# Own_18650_Board_v1_1_Final_AR.net
KiCad netlist of a schematic drawn in EAGLE
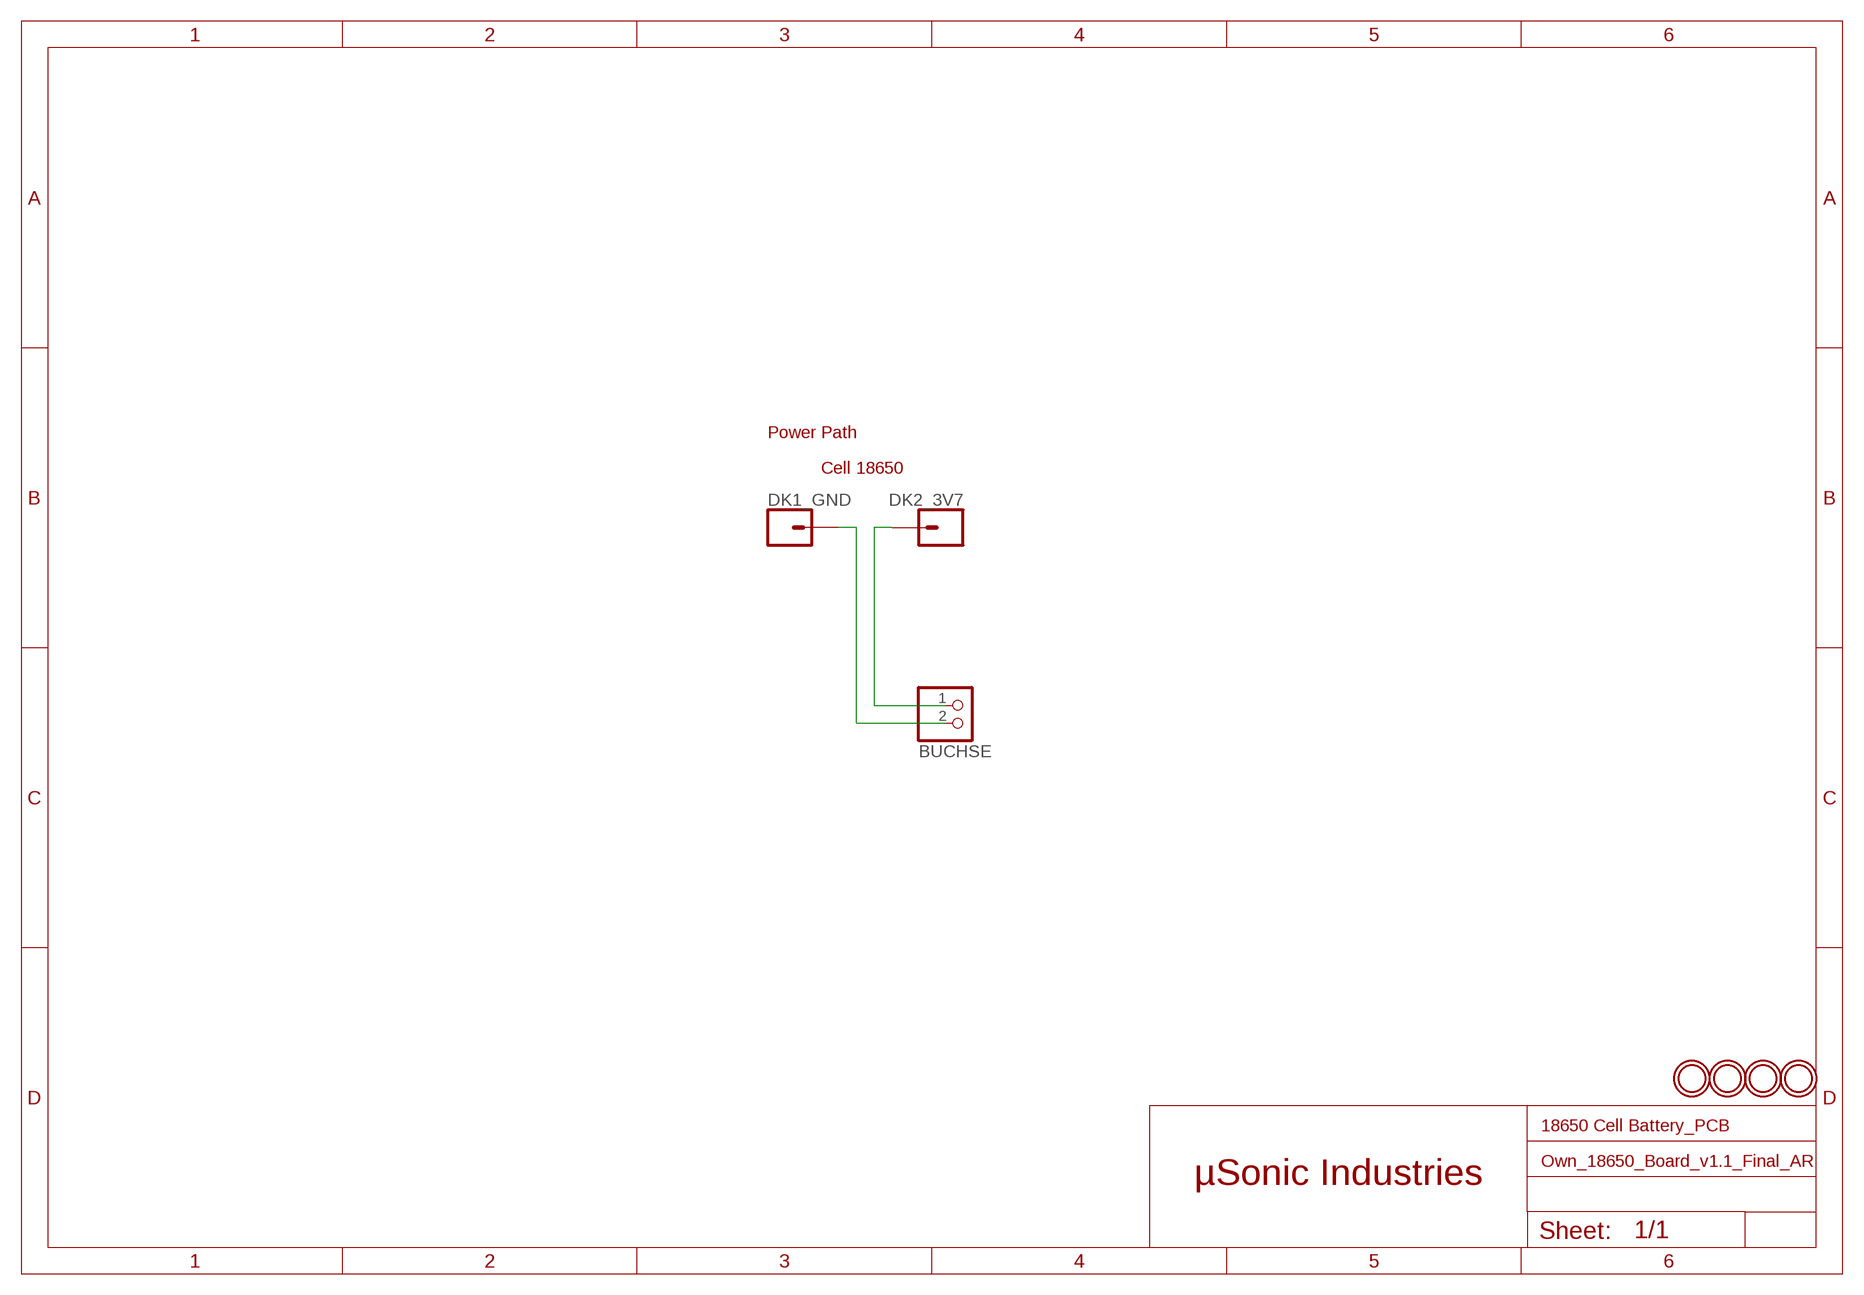
[diagram p0: schematic, sheet 1]

(export (version "E")
  (design (tool "Eeschema 10.0.6"))
  (components
    (comp (ref "BUCHSE")
      (value "JST_2PINOWN")
      (footprint "eagle-import:JST-PH-2-THMOWN")
      (libsource (lib "eagle-import") (part "JST_2PINOWN"))
    )
    (comp (ref "DK1_GND")
      (value "CONN_01")
      (footprint "eagle-import:1X01")
      (libsource (lib "eagle-import") (part "CONN_01"))
    )
    (comp (ref "DK2_3V7")
      (value "CONN_01")
      (footprint "eagle-import:1X01")
      (libsource (lib "eagle-import") (part "CONN_01"))
    )
    (comp (ref "U$1")
      (value "MOUNTINGHOLE2.5")
      (footprint "eagle-import:MOUNTINGHOLE_2.5_PLATED")
      (libsource (lib "eagle-import") (part "MOUNTINGHOLE2.5"))
    )
    (comp (ref "U$2")
      (value "MOUNTINGHOLE2.5")
      (footprint "eagle-import:MOUNTINGHOLE_2.5_PLATED")
      (libsource (lib "eagle-import") (part "MOUNTINGHOLE2.5"))
    )
    (comp (ref "U$3")
      (value "MOUNTINGHOLE2.5")
      (footprint "eagle-import:MOUNTINGHOLE_2.5_PLATED")
      (libsource (lib "eagle-import") (part "MOUNTINGHOLE2.5"))
    )
    (comp (ref "U$5")
      (value "MOUNTINGHOLE2.5")
      (footprint "eagle-import:MOUNTINGHOLE_2.5_PLATED")
      (libsource (lib "eagle-import") (part "MOUNTINGHOLE2.5"))
    )
  )
  (nets
    (net (code "1") (name "Net-(BUCHSE-1)") (class "Default")
      (node (ref "BUCHSE") (pin "2") (pinfunction "1_2") (pintype "passive"))
      (node (ref "DK1_GND") (pin "1") (pinfunction "1_1") (pintype "passive"))
    )
    (net (code "2") (name "Net-(BUCHSE-2)") (class "Default")
      (node (ref "BUCHSE") (pin "1") (pinfunction "2_1") (pintype "passive"))
      (node (ref "DK2_3V7") (pin "1") (pinfunction "1_1") (pintype "passive"))
    )
  )
)
